# sb-sonata-usbrp.net
KiCad netlist of a schematic drawn in Altium Designer
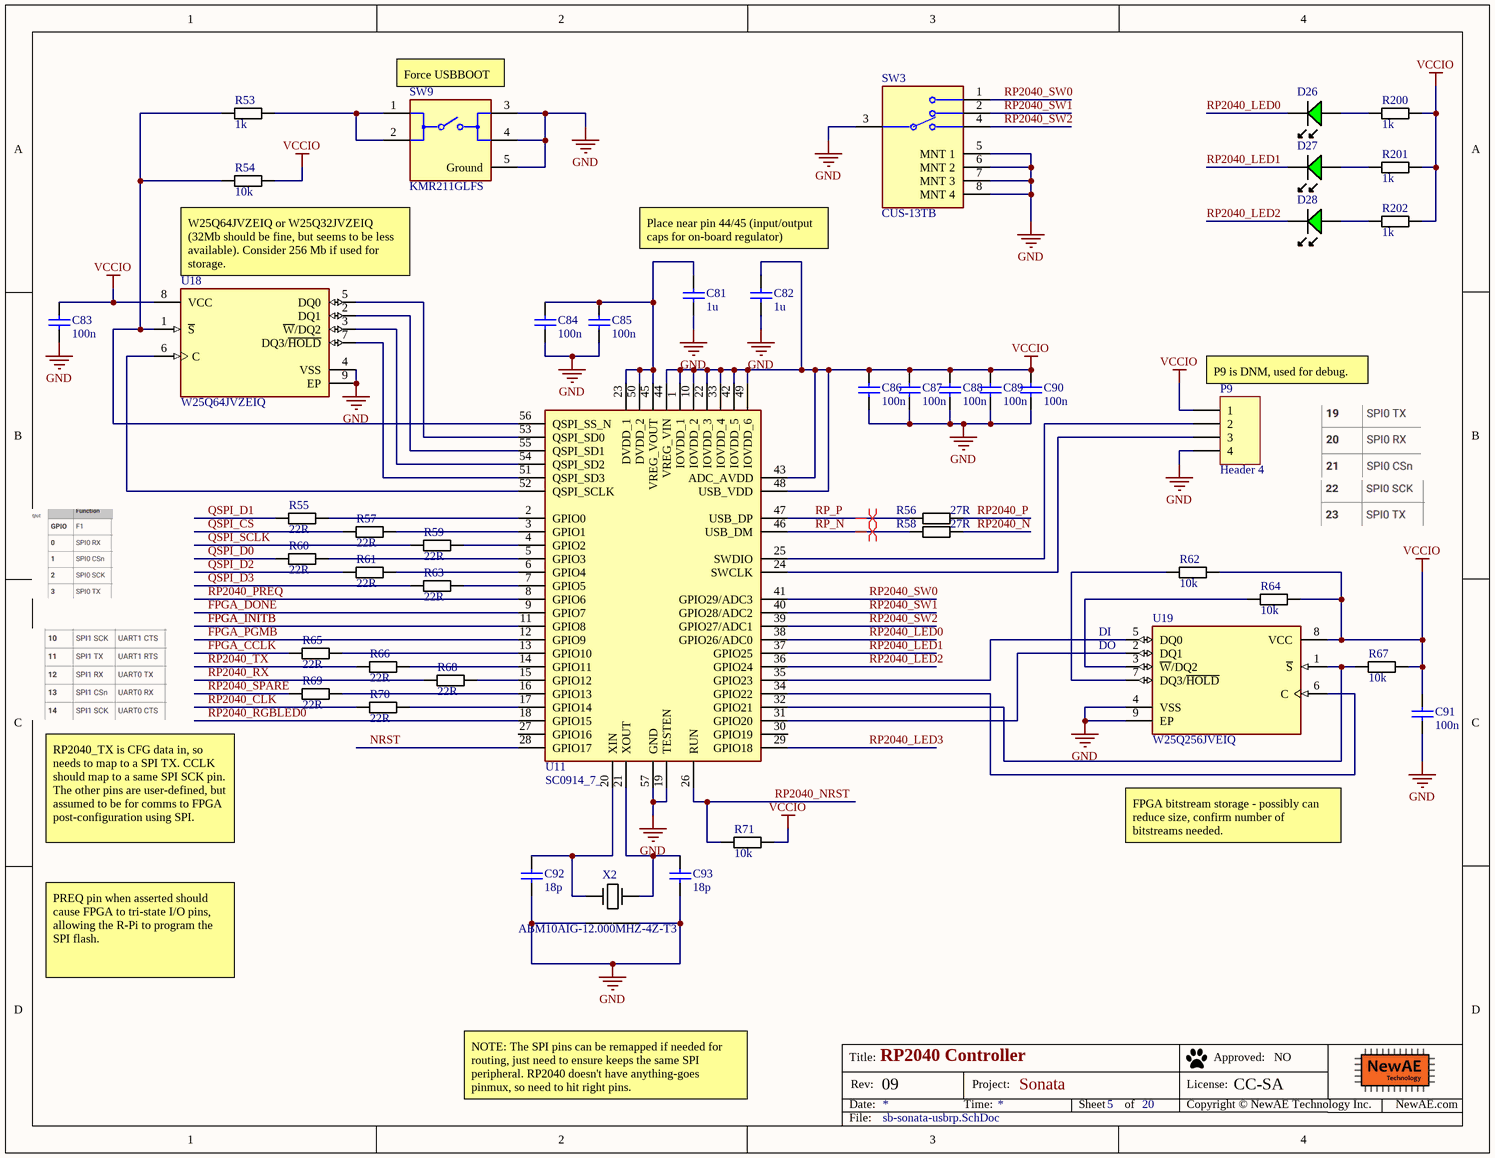
[diagram p0: sb-sonata-usbrp.SchDoc]

(export (version "E")
  (design (tool "Eeschema 10.0.6"))
  (components
    (comp (ref "C81")
      (value "1u")
      (footprint "CAPC0603_M")
      (description "1u, 0603, 50V")
      (fields (field (name "PART NUMBER") "CCHIP-1u-0603"))
      (libsource (lib "NewAE_AltiumLib") (part "CAP"))
    )
    (comp (ref "C82")
      (value "1u")
      (footprint "CAPC0603_M")
      (description "1u, 0603, 50V")
      (fields (field (name "PART NUMBER") "CCHIP-1u-0603"))
      (libsource (lib "NewAE_AltiumLib") (part "CAP"))
    )
    (comp (ref "C83")
      (value "100n")
      (footprint "CAPC0402_M")
      (description "100n, 0402")
      (fields (field (name "PART NUMBER") "CCHIP-100n-0402"))
      (libsource (lib "NewAE_AltiumLib") (part "CAP"))
    )
    (comp (ref "C84")
      (value "100n")
      (footprint "CAPC0402_M")
      (description "100n, 0402")
      (fields (field (name "PART NUMBER") "CCHIP-100n-0402"))
      (libsource (lib "NewAE_AltiumLib") (part "CAP"))
    )
    (comp (ref "C85")
      (value "100n")
      (footprint "CAPC0402_M")
      (description "100n, 0402")
      (fields (field (name "PART NUMBER") "CCHIP-100n-0402"))
      (libsource (lib "NewAE_AltiumLib") (part "CAP"))
    )
    (comp (ref "C86")
      (value "100n")
      (footprint "CAPC0402_M")
      (description "100n, 0402")
      (fields (field (name "PART NUMBER") "CCHIP-100n-0402"))
      (libsource (lib "NewAE_AltiumLib") (part "CAP"))
    )
    (comp (ref "C87")
      (value "100n")
      (footprint "CAPC0402_M")
      (description "100n, 0402")
      (fields (field (name "PART NUMBER") "CCHIP-100n-0402"))
      (libsource (lib "NewAE_AltiumLib") (part "CAP"))
    )
    (comp (ref "C88")
      (value "100n")
      (footprint "CAPC0402_M")
      (description "100n, 0402")
      (fields (field (name "PART NUMBER") "CCHIP-100n-0402"))
      (libsource (lib "NewAE_AltiumLib") (part "CAP"))
    )
    (comp (ref "C89")
      (value "100n")
      (footprint "CAPC0402_M")
      (description "100n, 0402")
      (fields (field (name "PART NUMBER") "CCHIP-100n-0402"))
      (libsource (lib "NewAE_AltiumLib") (part "CAP"))
    )
    (comp (ref "C90")
      (value "100n")
      (footprint "CAPC0402_M")
      (description "100n, 0402")
      (fields (field (name "PART NUMBER") "CCHIP-100n-0402"))
      (libsource (lib "NewAE_AltiumLib") (part "CAP"))
    )
    (comp (ref "C91")
      (value "100n")
      (footprint "CAPC0402_M")
      (description "100n, 0402")
      (fields (field (name "PART NUMBER") "CCHIP-100n-0402"))
      (libsource (lib "NewAE_AltiumLib") (part "CAP"))
    )
    (comp (ref "C92")
      (value "18p")
      (footprint "CAPC0402_M")
      (description "18p, 0402")
      (fields (field (name "PART NUMBER") "CCHIP-18p-0402"))
      (libsource (lib "NewAE_AltiumLib") (part "CAP"))
    )
    (comp (ref "C93")
      (value "18p")
      (footprint "CAPC0402_M")
      (description "18p, 0402")
      (fields (field (name "PART NUMBER") "CCHIP-18p-0402"))
      (libsource (lib "NewAE_AltiumLib") (part "CAP"))
    )
    (comp (ref "D26")
      (value "LED, 0603, Green")
      (footprint "LED-0603-GREEN")
      (description "Chip LED, Green")
      (fields (field (name "PART NUMBER") "LEDCHIP_0603_GREEN"))
      (libsource (lib "NewAE_AltiumLib") (part "LED_GREEN"))
    )
    (comp (ref "D27")
      (value "LED, 0603, Green")
      (footprint "LED-0603-GREEN")
      (description "Chip LED, Green")
      (fields (field (name "PART NUMBER") "LEDCHIP_0603_GREEN"))
      (libsource (lib "NewAE_AltiumLib") (part "LED_GREEN"))
    )
    (comp (ref "D28")
      (value "LED, 0603, Green")
      (footprint "LED-0603-GREEN")
      (description "Chip LED, Green")
      (fields (field (name "PART NUMBER") "LEDCHIP_0603_GREEN"))
      (libsource (lib "NewAE_AltiumLib") (part "LED_GREEN"))
    )
    (comp (ref "P9")
      (value "Header 4")
      (footprint "HDR1X4")
      (description "Header, 4-Pin")
      (fields (field (name "PUBLISHER") "Altium Limited"))
      (libsource (lib "Miscellaneous Connectors") (part "Header 4"))
    )
    (comp (ref "R53")
      (value "1k")
      (footprint "RESC1005X40N")
      (description "1k res, 0402, 1%, 1/16W")
      (fields (field (name "PART NUMBER") "RCHIP-1K-0402") (field (name "TOLERANCE") "1%"))
      (libsource (lib "NewAE_AltiumLib") (part "RES-EU"))
    )
    (comp (ref "R54")
      (value "10k")
      (footprint "RESC1005X40N")
      (description "10k res, 0402, 1%, 1/16W")
      (fields (field (name "PART NUMBER") "RCHIP-10K-0402") (field (name "TOLERANCE") "1%"))
      (libsource (lib "") (part "RES-EU_1"))
    )
    (comp (ref "R55")
      (value "22R")
      (footprint "RESC1005X40N")
      (description "22R res, 0402, 1%, 1/16W")
      (fields (field (name "PART NUMBER") "RCHIP-22R-0402") (field (name "TOLERANCE") "1%"))
      (libsource (lib "NewAE_AltiumLib") (part "RES-EU"))
    )
    (comp (ref "R56")
      (value "27R")
      (footprint "RESC1005X40N")
      (description "27R res, 0402, 1%, 1/16W")
      (fields (field (name "PART NUMBER") "RCHIP-27R-0402") (field (name "TOLERANCE") "1%"))
      (libsource (lib "") (part "RES-EU_1"))
    )
    (comp (ref "R57")
      (value "22R")
      (footprint "RESC1005X40N")
      (description "22R res, 0402, 1%, 1/16W")
      (fields (field (name "PART NUMBER") "RCHIP-22R-0402") (field (name "TOLERANCE") "1%"))
      (libsource (lib "NewAE_AltiumLib") (part "RES-EU"))
    )
    (comp (ref "R58")
      (value "27R")
      (footprint "RESC1005X40N")
      (description "27R res, 0402, 1%, 1/16W")
      (fields (field (name "PART NUMBER") "RCHIP-27R-0402") (field (name "TOLERANCE") "1%"))
      (libsource (lib "") (part "RES-EU_1"))
    )
    (comp (ref "R59")
      (value "22R")
      (footprint "RESC1005X40N")
      (description "22R res, 0402, 1%, 1/16W")
      (fields (field (name "PART NUMBER") "RCHIP-22R-0402") (field (name "TOLERANCE") "1%"))
      (libsource (lib "NewAE_AltiumLib") (part "RES-EU"))
    )
    (comp (ref "R60")
      (value "22R")
      (footprint "RESC1005X40N")
      (description "22R res, 0402, 1%, 1/16W")
      (fields (field (name "PART NUMBER") "RCHIP-22R-0402") (field (name "TOLERANCE") "1%"))
      (libsource (lib "NewAE_AltiumLib") (part "RES-EU"))
    )
    (comp (ref "R61")
      (value "22R")
      (footprint "RESC1005X40N")
      (description "22R res, 0402, 1%, 1/16W")
      (fields (field (name "PART NUMBER") "RCHIP-22R-0402") (field (name "TOLERANCE") "1%"))
      (libsource (lib "NewAE_AltiumLib") (part "RES-EU"))
    )
    (comp (ref "R62")
      (value "10k")
      (footprint "RESC1005X40N")
      (description "10k res, 0402, 1%, 1/16W")
      (fields (field (name "PART NUMBER") "RCHIP-10K-0402") (field (name "TOLERANCE") "1%"))
      (libsource (lib "") (part "RES-EU_1"))
    )
    (comp (ref "R63")
      (value "22R")
      (footprint "RESC1005X40N")
      (description "22R res, 0402, 1%, 1/16W")
      (fields (field (name "PART NUMBER") "RCHIP-22R-0402") (field (name "TOLERANCE") "1%"))
      (libsource (lib "NewAE_AltiumLib") (part "RES-EU"))
    )
    (comp (ref "R64")
      (value "10k")
      (footprint "RESC1005X40N")
      (description "10k res, 0402, 1%, 1/16W")
      (fields (field (name "PART NUMBER") "RCHIP-10K-0402") (field (name "TOLERANCE") "1%"))
      (libsource (lib "") (part "RES-EU_1"))
    )
    (comp (ref "R65")
      (value "22R")
      (footprint "RESC1005X40N")
      (description "22R res, 0402, 1%, 1/16W")
      (fields (field (name "PART NUMBER") "RCHIP-22R-0402") (field (name "TOLERANCE") "1%"))
      (libsource (lib "NewAE_AltiumLib") (part "RES-EU"))
    )
    (comp (ref "R66")
      (value "22R")
      (footprint "RESC1005X40N")
      (description "22R res, 0402, 1%, 1/16W")
      (fields (field (name "PART NUMBER") "RCHIP-22R-0402") (field (name "TOLERANCE") "1%"))
      (libsource (lib "NewAE_AltiumLib") (part "RES-EU"))
    )
    (comp (ref "R67")
      (value "10k")
      (footprint "RESC1005X40N")
      (description "10k res, 0402, 1%, 1/16W")
      (fields (field (name "PART NUMBER") "RCHIP-10K-0402") (field (name "TOLERANCE") "1%"))
      (libsource (lib "NewAE_AltiumLib") (part "RES-EU"))
    )
    (comp (ref "R68")
      (value "22R")
      (footprint "RESC1005X40N")
      (description "22R res, 0402, 1%, 1/16W")
      (fields (field (name "PART NUMBER") "RCHIP-22R-0402") (field (name "TOLERANCE") "1%"))
      (libsource (lib "NewAE_AltiumLib") (part "RES-EU"))
    )
    (comp (ref "R69")
      (value "22R")
      (footprint "RESC1005X40N")
      (description "22R res, 0402, 1%, 1/16W")
      (fields (field (name "PART NUMBER") "RCHIP-22R-0402") (field (name "TOLERANCE") "1%"))
      (libsource (lib "NewAE_AltiumLib") (part "RES-EU"))
    )
    (comp (ref "R70")
      (value "22R")
      (footprint "RESC1005X40N")
      (description "22R res, 0402, 1%, 1/16W")
      (fields (field (name "PART NUMBER") "RCHIP-22R-0402") (field (name "TOLERANCE") "1%"))
      (libsource (lib "NewAE_AltiumLib") (part "RES-EU"))
    )
    (comp (ref "R71")
      (value "10k")
      (footprint "RESC1005X40N")
      (description "10k res, 0402, 1%, 1/16W")
      (fields (field (name "PART NUMBER") "RCHIP-10K-0402") (field (name "TOLERANCE") "1%"))
      (libsource (lib "NewAE_AltiumLib") (part "RES-EU"))
    )
    (comp (ref "R200")
      (value "1k")
      (footprint "RESC1005X40N")
      (description "1k res, 0402, 1%, 1/16W")
      (fields (field (name "PART NUMBER") "RCHIP-1K-0402") (field (name "TOLERANCE") "1%"))
      (libsource (lib "NewAE_AltiumLib") (part "RES-EU"))
    )
    (comp (ref "R201")
      (value "1k")
      (footprint "RESC1005X40N")
      (description "1k res, 0402, 1%, 1/16W")
      (fields (field (name "PART NUMBER") "RCHIP-1K-0402") (field (name "TOLERANCE") "1%"))
      (libsource (lib "NewAE_AltiumLib") (part "RES-EU"))
    )
    (comp (ref "R202")
      (value "1k")
      (footprint "RESC1005X40N")
      (description "1k res, 0402, 1%, 1/16W")
      (fields (field (name "PART NUMBER") "RCHIP-1K-0402") (field (name "TOLERANCE") "1%"))
      (libsource (lib "NewAE_AltiumLib") (part "RES-EU"))
    )
    (comp (ref "SW3")
      (value "CUS-13TB")
      (footprint "FP-CUS-13TB-MFG")
      (description "SWITCH SLIDE SP3T 300MA 4V")
      (libsource (lib "Altium Content Vault") (part "47bcb96ef67674530f45e4053201745"))
    )
    (comp (ref "SW9")
      (value "KMR211GLFS")
      (footprint "FP-KMR211GLFS-MFG")
      (description "SWITCH TACTILE SPST-NO 0.05A 32V")
      (libsource (lib "Altium Content Vault") (part "99988cc0f9d3d39bd794ae22da860e5"))
    )
    (comp (ref "U11")
      (value "SC0914_7_")
      (footprint "QFN40P700X700X90-57N-D")
      (description "Connector")
      (fields
        (field (name "MANUFACTURER_PART_NUMBER") "SC0914(7)")
        (field (name "MOUSER PART NUMBER") "358-SC09147")
      )
      (libsource (lib "*") (part "SC0914_7_"))
    )
    (comp (ref "U18")
      (value "W25Q64JVZEIQ")
      (footprint "WSON68_Micron")
      (description "IC FLASH 64M SPI 133MHZ 8WPDFN")
      (libsource (lib "") (part "QSPI_WSON_1"))
    )
    (comp (ref "U19")
      (value "W25Q256JVEIQ")
      (footprint "WSON68_Micron")
      (description "IC FLASH 256M SPI 133MHZ 8WPDFN")
      (libsource (lib "NewAE_AltiumLib") (part "QSPI_WSON"))
    )
    (comp (ref "X2")
      (value "ABM10AIG-12.000MHZ-4Z-T3")
      (footprint "2.5x2mm XTAL")
      (description "12MHz, SMD")
      (libsource (lib "NewAE_AltiumLib") (part "XTAL_4PIN_13"))
    )
  )
  (nets
    (net (code "1") (name "/FPGA_CCLK") (class "Default")
      (node (ref "R65") (pin "1") (pinfunction "1_1") (pintype "passive"))
    )
    (net (code "2") (name "/FPGA_DONE") (class "Default")
      (node (ref "U11") (pin "9") (pinfunction "GPIO7_9") (pintype "passive"))
    )
    (net (code "3") (name "/FPGA_INITB") (class "Default")
      (node (ref "U11") (pin "11") (pinfunction "GPIO8_11") (pintype "passive"))
    )
    (net (code "4") (name "/FPGA_PGMB") (class "Default")
      (node (ref "U11") (pin "12") (pinfunction "GPIO9_12") (pintype "passive"))
    )
    (net (code "5") (name "/NRST") (class "Default")
      (node (ref "U11") (pin "28") (pinfunction "GPIO17_28") (pintype "passive"))
    )
    (net (code "6") (name "/QSPI_CS") (class "Default")
      (node (ref "R57") (pin "1") (pinfunction "1_1") (pintype "passive"))
    )
    (net (code "7") (name "/QSPI_D0") (class "Default")
      (node (ref "R60") (pin "1") (pinfunction "1_1") (pintype "passive"))
    )
    (net (code "8") (name "/QSPI_D1") (class "Default")
      (node (ref "R55") (pin "1") (pinfunction "1_1") (pintype "passive"))
    )
    (net (code "9") (name "/QSPI_D2") (class "Default")
      (node (ref "R61") (pin "1") (pinfunction "1_1") (pintype "passive"))
    )
    (net (code "10") (name "/QSPI_D3") (class "Default")
      (node (ref "R63") (pin "1") (pinfunction "1_1") (pintype "passive"))
    )
    (net (code "11") (name "/QSPI_SCLK") (class "Default")
      (node (ref "R59") (pin "1") (pinfunction "1_1") (pintype "passive"))
    )
    (net (code "12") (name "/RP2040_CLK") (class "Default")
      (node (ref "R70") (pin "1") (pinfunction "1_1") (pintype "passive"))
    )
    (net (code "13") (name "/RP2040_LED0") (class "Default")
      (node (ref "D26") (pin "K") (pinfunction "K_K") (pintype "passive"))
      (node (ref "U11") (pin "38") (pinfunction "GPIO26/ADC0_38") (pintype "passive"))
    )
    (net (code "14") (name "/RP2040_LED1") (class "Default")
      (node (ref "D27") (pin "K") (pinfunction "K_K") (pintype "passive"))
      (node (ref "U11") (pin "37") (pinfunction "GPIO25_37") (pintype "passive"))
    )
    (net (code "15") (name "/RP2040_LED2") (class "Default")
      (node (ref "D28") (pin "K") (pinfunction "K_K") (pintype "passive"))
      (node (ref "U11") (pin "36") (pinfunction "GPIO24_36") (pintype "passive"))
    )
    (net (code "16") (name "/RP2040_LED3") (class "Default")
      (node (ref "U11") (pin "29") (pinfunction "GPIO18_29") (pintype "passive"))
    )
    (net (code "17") (name "/RP2040_N") (class "Default")
      (node (ref "R58") (pin "1") (pinfunction "1_1") (pintype "passive"))
    )
    (net (code "18") (name "/RP2040_NRST") (class "Default")
      (node (ref "R71") (pin "1") (pinfunction "1_1") (pintype "passive"))
      (node (ref "U11") (pin "26") (pinfunction "RUN_26") (pintype "passive"))
    )
    (net (code "19") (name "/RP2040_P") (class "Default")
      (node (ref "R56") (pin "1") (pinfunction "1_1") (pintype "passive"))
    )
    (net (code "20") (name "/RP2040_PREQ") (class "Default")
      (node (ref "U11") (pin "8") (pinfunction "GPIO6_8") (pintype "passive"))
    )
    (net (code "21") (name "/RP2040_RGBLED0") (class "Default")
      (node (ref "U11") (pin "18") (pinfunction "GPIO15_18") (pintype "passive"))
    )
    (net (code "22") (name "/RP2040_RX") (class "Default")
      (node (ref "R68") (pin "1") (pinfunction "1_1") (pintype "passive"))
    )
    (net (code "23") (name "/RP2040_SPARE") (class "Default")
      (node (ref "R69") (pin "1") (pinfunction "1_1") (pintype "passive"))
    )
    (net (code "24") (name "/RP2040_SW0") (class "Default")
      (node (ref "SW3") (pin "1") (pinfunction "1_1") (pintype "passive"))
      (node (ref "U11") (pin "41") (pinfunction "GPIO29/ADC3_41") (pintype "passive"))
    )
    (net (code "25") (name "/RP2040_SW1") (class "Default")
      (node (ref "SW3") (pin "2") (pinfunction "2_2") (pintype "passive"))
      (node (ref "U11") (pin "40") (pinfunction "GPIO28/ADC2_40") (pintype "passive"))
    )
    (net (code "26") (name "/RP2040_SW2") (class "Default")
      (node (ref "SW3") (pin "4") (pinfunction "4_4") (pintype "passive"))
      (node (ref "U11") (pin "39") (pinfunction "GPIO27/ADC1_39") (pintype "passive"))
    )
    (net (code "27") (name "/RP2040_TX") (class "Default")
      (node (ref "R66") (pin "1") (pinfunction "1_1") (pintype "passive"))
    )
    (net (code "28") (name "/RP_N") (class "Default")
      (node (ref "R58") (pin "2") (pinfunction "2_2") (pintype "passive"))
      (node (ref "U11") (pin "46") (pinfunction "USB_DM_46") (pintype "passive"))
    )
    (net (code "29") (name "/RP_P") (class "Default")
      (node (ref "R56") (pin "2") (pinfunction "2_2") (pintype "passive"))
      (node (ref "U11") (pin "47") (pinfunction "USB_DP_47") (pintype "passive"))
    )
    (net (code "30") (name "GND") (class "Default")
      (node (ref "C81") (pin "2") (pinfunction "2_2") (pintype "passive"))
      (node (ref "C82") (pin "2") (pinfunction "2_2") (pintype "passive"))
      (node (ref "C83") (pin "2") (pinfunction "2_2") (pintype "passive"))
      (node (ref "C84") (pin "2") (pinfunction "2_2") (pintype "passive"))
      (node (ref "C85") (pin "2") (pinfunction "2_2") (pintype "passive"))
      (node (ref "C86") (pin "2") (pinfunction "2_2") (pintype "passive"))
      (node (ref "C87") (pin "2") (pinfunction "2_2") (pintype "passive"))
      (node (ref "C88") (pin "2") (pinfunction "2_2") (pintype "passive"))
      (node (ref "C89") (pin "2") (pinfunction "2_2") (pintype "passive"))
      (node (ref "C90") (pin "2") (pinfunction "2_2") (pintype "passive"))
      (node (ref "C91") (pin "2") (pinfunction "2_2") (pintype "passive"))
      (node (ref "C92") (pin "2") (pinfunction "2_2") (pintype "passive"))
      (node (ref "C93") (pin "2") (pinfunction "2_2") (pintype "passive"))
      (node (ref "P9") (pin "4") (pinfunction "4_4") (pintype "passive"))
      (node (ref "SW3") (pin "3") (pinfunction "C_3") (pintype "passive"))
      (node (ref "SW3") (pin "5") (pinfunction "MNT_1_5") (pintype "passive"))
      (node (ref "SW3") (pin "6") (pinfunction "MNT_2_6") (pintype "passive"))
      (node (ref "SW3") (pin "7") (pinfunction "MNT_3_7") (pintype "passive"))
      (node (ref "SW3") (pin "8") (pinfunction "MNT_4_8") (pintype "passive"))
      (node (ref "SW9") (pin "3") (pinfunction "3_3") (pintype "passive"))
      (node (ref "SW9") (pin "4") (pinfunction "4_4") (pintype "passive"))
      (node (ref "SW9") (pin "5") (pinfunction "Ground_5") (pintype "power_in"))
      (node (ref "U11") (pin "19") (pinfunction "TESTEN_19") (pintype "passive"))
      (node (ref "U11") (pin "57") (pinfunction "GND_57") (pintype "passive"))
      (node (ref "U18") (pin "4") (pinfunction "VSS_4") (pintype "power_in"))
      (node (ref "U18") (pin "9") (pinfunction "EP_9") (pintype "power_in"))
      (node (ref "U19") (pin "4") (pinfunction "VSS_4") (pintype "power_in"))
      (node (ref "U19") (pin "9") (pinfunction "EP_9") (pintype "power_in"))
      (node (ref "X2") (pin "2") (pinfunction "GND_2") (pintype "power_in"))
      (node (ref "X2") (pin "4") (pinfunction "GND_4") (pintype "power_in"))
    )
    (net (code "31") (name "Net-(D26-PadA)") (class "Default")
      (node (ref "D26") (pin "A") (pinfunction "A_A") (pintype "passive"))
      (node (ref "R200") (pin "1") (pinfunction "1_1") (pintype "passive"))
    )
    (net (code "32") (name "Net-(D27-PadA)") (class "Default")
      (node (ref "D27") (pin "A") (pinfunction "A_A") (pintype "passive"))
      (node (ref "R201") (pin "1") (pinfunction "1_1") (pintype "passive"))
    )
    (net (code "33") (name "Net-(D28-PadA)") (class "Default")
      (node (ref "D28") (pin "A") (pinfunction "A_A") (pintype "passive"))
      (node (ref "R202") (pin "1") (pinfunction "1_1") (pintype "passive"))
    )
    (net (code "34") (name "Net-(R53-Pad2)") (class "Default")
      (node (ref "R53") (pin "2") (pinfunction "2_2") (pintype "passive"))
      (node (ref "SW9") (pin "1") (pinfunction "1_1") (pintype "passive"))
      (node (ref "SW9") (pin "2") (pinfunction "2_2") (pintype "passive"))
    )
    (net (code "35") (name "Net-(U11-DVDD_1)") (class "Default")
      (node (ref "C81") (pin "1") (pinfunction "1_1") (pintype "passive"))
      (node (ref "C84") (pin "1") (pinfunction "1_1") (pintype "passive"))
      (node (ref "C85") (pin "1") (pinfunction "1_1") (pintype "passive"))
      (node (ref "U11") (pin "23") (pinfunction "DVDD_1_23") (pintype "passive"))
      (node (ref "U11") (pin "45") (pinfunction "VREG_VOUT_45") (pintype "passive"))
      (node (ref "U11") (pin "50") (pinfunction "DVDD_2_50") (pintype "passive"))
    )
    (net (code "36") (name "Net-(U11-GPIO0)") (class "Default")
      (node (ref "R55") (pin "2") (pinfunction "2_2") (pintype "passive"))
      (node (ref "U11") (pin "2") (pinfunction "GPIO0_2") (pintype "passive"))
    )
    (net (code "37") (name "Net-(U11-GPIO1)") (class "Default")
      (node (ref "R57") (pin "2") (pinfunction "2_2") (pintype "passive"))
      (node (ref "U11") (pin "3") (pinfunction "GPIO1_3") (pintype "passive"))
    )
    (net (code "38") (name "Net-(U11-GPIO2)") (class "Default")
      (node (ref "R59") (pin "2") (pinfunction "2_2") (pintype "passive"))
      (node (ref "U11") (pin "4") (pinfunction "GPIO2_4") (pintype "passive"))
    )
    (net (code "39") (name "Net-(U11-GPIO3)") (class "Default")
      (node (ref "R60") (pin "2") (pinfunction "2_2") (pintype "passive"))
      (node (ref "U11") (pin "5") (pinfunction "GPIO3_5") (pintype "passive"))
    )
    (net (code "40") (name "Net-(U11-GPIO4)") (class "Default")
      (node (ref "R61") (pin "2") (pinfunction "2_2") (pintype "passive"))
      (node (ref "U11") (pin "6") (pinfunction "GPIO4_6") (pintype "passive"))
    )
    (net (code "41") (name "Net-(U11-GPIO5)") (class "Default")
      (node (ref "R63") (pin "2") (pinfunction "2_2") (pintype "passive"))
      (node (ref "U11") (pin "7") (pinfunction "GPIO5_7") (pintype "passive"))
    )
    (net (code "42") (name "Net-(U11-GPIO10)") (class "Default")
      (node (ref "R65") (pin "2") (pinfunction "2_2") (pintype "passive"))
      (node (ref "U11") (pin "13") (pinfunction "GPIO10_13") (pintype "passive"))
    )
    (net (code "43") (name "Net-(U11-GPIO11)") (class "Default")
      (node (ref "R66") (pin "2") (pinfunction "2_2") (pintype "passive"))
      (node (ref "U11") (pin "14") (pinfunction "GPIO11_14") (pintype "passive"))
    )
    (net (code "44") (name "Net-(U11-GPIO12)") (class "Default")
      (node (ref "R68") (pin "2") (pinfunction "2_2") (pintype "passive"))
      (node (ref "U11") (pin "15") (pinfunction "GPIO12_15") (pintype "passive"))
    )
    (net (code "45") (name "Net-(U11-GPIO13)") (class "Default")
      (node (ref "R69") (pin "2") (pinfunction "2_2") (pintype "passive"))
      (node (ref "U11") (pin "16") (pinfunction "GPIO13_16") (pintype "passive"))
    )
    (net (code "46") (name "Net-(U11-GPIO14)") (class "Default")
      (node (ref "R70") (pin "2") (pinfunction "2_2") (pintype "passive"))
      (node (ref "U11") (pin "17") (pinfunction "GPIO14_17") (pintype "passive"))
    )
    (net (code "47") (name "Net-(U11-GPIO20)") (class "Default")
      (node (ref "U11") (pin "31") (pinfunction "GPIO20_31") (pintype "passive"))
      (node (ref "U19") (pin "2") (pinfunction "DQ1_2") (pintype "bidirectional"))
    )
    (net (code "48") (name "Net-(U11-GPIO21)") (class "Default")
      (node (ref "R67") (pin "1") (pinfunction "1_1") (pintype "passive"))
      (node (ref "U11") (pin "32") (pinfunction "GPIO21_32") (pintype "passive"))
      (node (ref "U19") (pin "1") (pinfunction "~{S}_1") (pintype "input"))
    )
    (net (code "49") (name "Net-(U11-GPIO22)") (class "Default")
      (node (ref "U11") (pin "34") (pinfunction "GPIO22_34") (pintype "passive"))
      (node (ref "U19") (pin "6") (pinfunction "C_6") (pintype "input"))
    )
    (net (code "50") (name "Net-(U11-GPIO23)") (class "Default")
      (node (ref "U11") (pin "35") (pinfunction "GPIO23_35") (pintype "passive"))
      (node (ref "U19") (pin "5") (pinfunction "DQ0_5") (pintype "bidirectional"))
    )
    (net (code "51") (name "Net-(U11-QSPI_SCLK)") (class "Default")
      (node (ref "U11") (pin "52") (pinfunction "QSPI_SCLK_52") (pintype "passive"))
      (node (ref "U18") (pin "6") (pinfunction "C_6") (pintype "input"))
    )
    (net (code "52") (name "Net-(U11-QSPI_SD0)") (class "Default")
      (node (ref "U11") (pin "53") (pinfunction "QSPI_SD0_53") (pintype "passive"))
      (node (ref "U18") (pin "5") (pinfunction "DQ0_5") (pintype "bidirectional"))
    )
    (net (code "53") (name "Net-(U11-QSPI_SD1)") (class "Default")
      (node (ref "U11") (pin "55") (pinfunction "QSPI_SD1_55") (pintype "passive"))
      (node (ref "U18") (pin "2") (pinfunction "DQ1_2") (pintype "bidirectional"))
    )
    (net (code "54") (name "Net-(U11-QSPI_SD2)") (class "Default")
      (node (ref "U11") (pin "54") (pinfunction "QSPI_SD2_54") (pintype "passive"))
      (node (ref "U18") (pin "3") (pinfunction "~{W}/DQ2_3") (pintype "bidirectional"))
    )
    (net (code "55") (name "Net-(U11-QSPI_SD3)") (class "Default")
      (node (ref "U11") (pin "51") (pinfunction "QSPI_SD3_51") (pintype "passive"))
      (node (ref "U18") (pin "7") (pinfunction "DQ3/~{HOLD}_7") (pintype "bidirectional"))
    )
    (net (code "56") (name "Net-(U11-QSPI_SS_N)") (class "Default")
      (node (ref "R53") (pin "1") (pinfunction "1_1") (pintype "passive"))
      (node (ref "R54") (pin "2") (pinfunction "2_2") (pintype "passive"))
      (node (ref "U11") (pin "56") (pinfunction "QSPI_SS_N_56") (pintype "passive"))
      (node (ref "U18") (pin "1") (pinfunction "~{S}_1") (pintype "input"))
    )
    (net (code "57") (name "Net-(U11-SWCLK)") (class "Default")
      (node (ref "P9") (pin "3") (pinfunction "3_3") (pintype "passive"))
      (node (ref "U11") (pin "24") (pinfunction "SWCLK_24") (pintype "passive"))
    )
    (net (code "58") (name "Net-(U11-SWDIO)") (class "Default")
      (node (ref "P9") (pin "2") (pinfunction "2_2") (pintype "passive"))
      (node (ref "U11") (pin "25") (pinfunction "SWDIO_25") (pintype "passive"))
    )
    (net (code "59") (name "Net-(U11-XIN)") (class "Default")
      (node (ref "C92") (pin "1") (pinfunction "1_1") (pintype "passive"))
      (node (ref "U11") (pin "20") (pinfunction "XIN_20") (pintype "passive"))
      (node (ref "X2") (pin "1") (pinfunction "IN_1") (pintype "passive"))
    )
    (net (code "60") (name "Net-(U11-XOUT)") (class "Default")
      (node (ref "C93") (pin "1") (pinfunction "1_1") (pintype "passive"))
      (node (ref "U11") (pin "21") (pinfunction "XOUT_21") (pintype "passive"))
      (node (ref "X2") (pin "3") (pinfunction "OUT_3") (pintype "passive"))
    )
    (net (code "61") (name "Net-(U19-DQ3{slash}~{HOLD})") (class "Default")
      (node (ref "R62") (pin "2") (pinfunction "2_2") (pintype "passive"))
      (node (ref "U19") (pin "7") (pinfunction "DQ3/~{HOLD}_7") (pintype "bidirectional"))
    )
    (net (code "62") (name "Net-(U19-~{W}{slash}DQ2)") (class "Default")
      (node (ref "R64") (pin "2") (pinfunction "2_2") (pintype "passive"))
      (node (ref "U19") (pin "3") (pinfunction "~{W}/DQ2_3") (pintype "bidirectional"))
    )
    (net (code "63") (name "VCCIO") (class "Default")
      (node (ref "C82") (pin "1") (pinfunction "1_1") (pintype "passive"))
      (node (ref "C83") (pin "1") (pinfunction "1_1") (pintype "passive"))
      (node (ref "C86") (pin "1") (pinfunction "1_1") (pintype "passive"))
      (node (ref "C87") (pin "1") (pinfunction "1_1") (pintype "passive"))
      (node (ref "C88") (pin "1") (pinfunction "1_1") (pintype "passive"))
      (node (ref "C89") (pin "1") (pinfunction "1_1") (pintype "passive"))
      (node (ref "C90") (pin "1") (pinfunction "1_1") (pintype "passive"))
      (node (ref "C91") (pin "1") (pinfunction "1_1") (pintype "passive"))
      (node (ref "P9") (pin "1") (pinfunction "1_1") (pintype "passive"))
      (node (ref "R200") (pin "2") (pinfunction "2_2") (pintype "passive"))
      (node (ref "R201") (pin "2") (pinfunction "2_2") (pintype "passive"))
      (node (ref "R202") (pin "2") (pinfunction "2_2") (pintype "passive"))
      (node (ref "R54") (pin "1") (pinfunction "1_1") (pintype "passive"))
      (node (ref "R62") (pin "1") (pinfunction "1_1") (pintype "passive"))
      (node (ref "R64") (pin "1") (pinfunction "1_1") (pintype "passive"))
      (node (ref "R67") (pin "2") (pinfunction "2_2") (pintype "passive"))
      (node (ref "R71") (pin "2") (pinfunction "2_2") (pintype "passive"))
      (node (ref "U11") (pin "1") (pinfunction "IOVDD_1_1") (pintype "passive"))
      (node (ref "U11") (pin "10") (pinfunction "IOVDD_2_10") (pintype "passive"))
      (node (ref "U11") (pin "22") (pinfunction "IOVDD_3_22") (pintype "passive"))
      (node (ref "U11") (pin "33") (pinfunction "IOVDD_4_33") (pintype "passive"))
      (node (ref "U11") (pin "42") (pinfunction "IOVDD_5_42") (pintype "passive"))
      (node (ref "U11") (pin "43") (pinfunction "ADC_AVDD_43") (pintype "passive"))
      (node (ref "U11") (pin "44") (pinfunction "VREG_VIN_44") (pintype "passive"))
      (node (ref "U11") (pin "48") (pinfunction "USB_VDD_48") (pintype "passive"))
      (node (ref "U11") (pin "49") (pinfunction "IOVDD_6_49") (pintype "passive"))
      (node (ref "U18") (pin "8") (pinfunction "VCC_8") (pintype "power_in"))
      (node (ref "U19") (pin "8") (pinfunction "VCC_8") (pintype "power_in"))
    )
    (net (code "64") (name "unconnected-(U11-GPIO16-Pad27)") (class "Default")
      (node (ref "U11") (pin "27") (pinfunction "GPIO16_27") (pintype "passive"))
    )
    (net (code "65") (name "unconnected-(U11-GPIO19-Pad30)") (class "Default")
      (node (ref "U11") (pin "30") (pinfunction "GPIO19_30") (pintype "passive"))
    )
  )
)
